# 16_SPI_TYPEC_PWR.net
KiCad netlist of a schematic drawn in Altium Designer
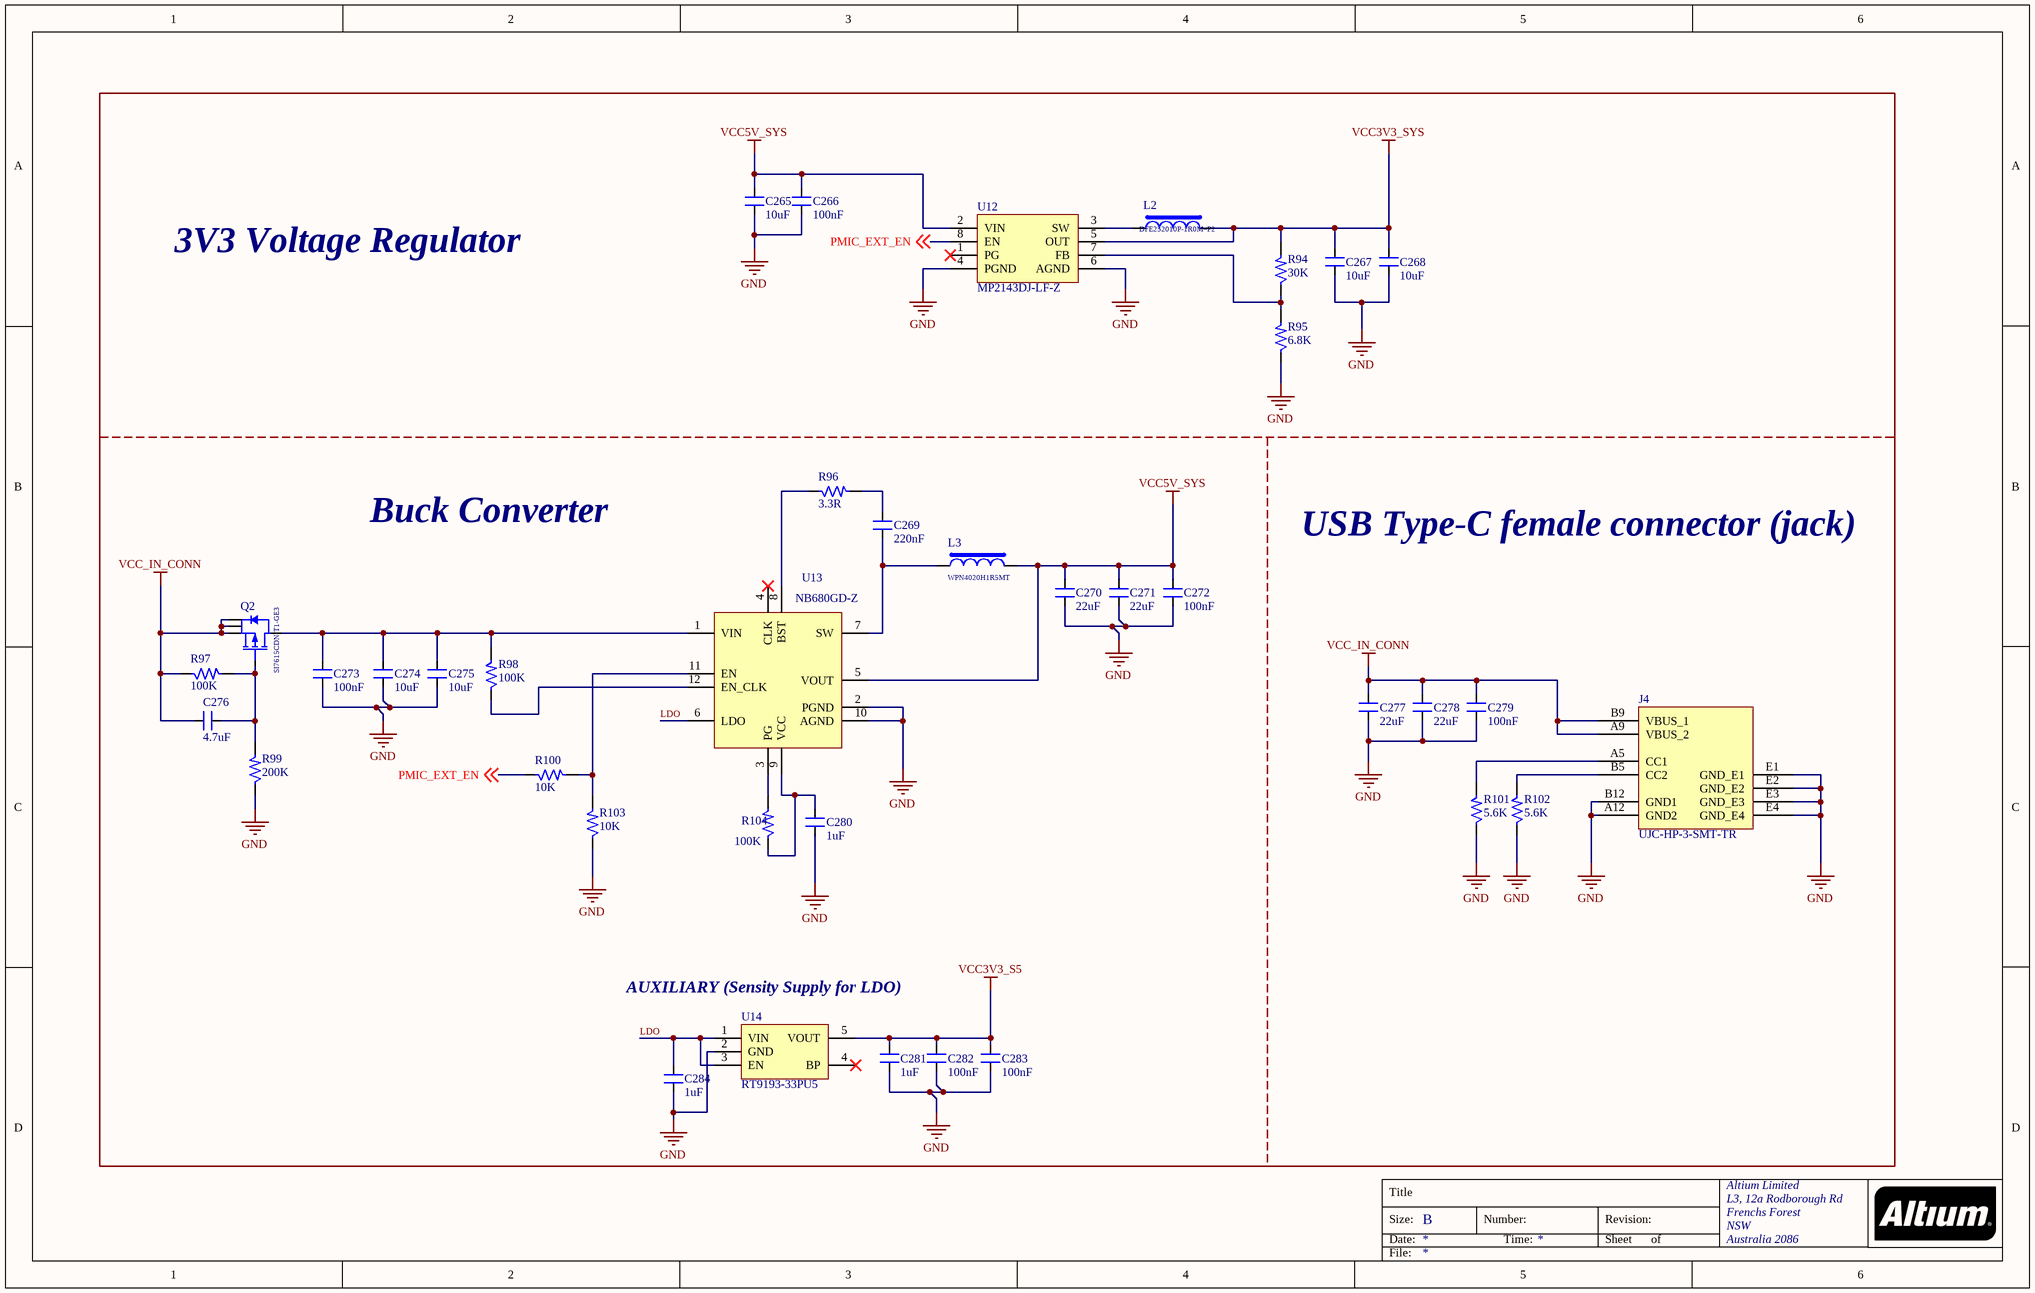
[diagram p0: [16] SPI_TYPEC_PWR.SchDoc]

(export (version "E")
  (design (tool "Eeschema 10.0.6"))
  (components
    (comp (ref "C265")
      (value "10uF")
      (footprint "CAP_0402")
      (description "10µF ±20% 10V Ceramic Capacitor X5R 0402 (1005 Metric)")
      (fields
        (field (name "MANUFACTURER PART NUMBER") "CL05A106MP5NUNC")
        (field (name "MANUFACTURER") "Samsung Electro-Mechanics")
      )
      (libsource (lib "EsteemPCB_SOM_Course_intlib") (part "CAP_10uF-10V-20%-0402"))
    )
    (comp (ref "C266")
      (value "100nF")
      (footprint "CAP_0402")
      (description "0.1µF ±10% 10V Ceramic Capacitor X7R 0402 (1005 Metric)")
      (fields
        (field (name "MANUFACTURER") "Yageo")
        (field (name "MANUFACTURER PART NUMBER") "CC0402KRX7R6BB104")
      )
      (libsource (lib "EsteemPCB_SOM_Course_intlib") (part "CAP_100nF-10V-10%-0402"))
    )
    (comp (ref "C267")
      (value "10uF")
      (footprint "CAP_0402")
      (description "10µF ±20% 10V Ceramic Capacitor X5R 0402 (1005 Metric)")
      (fields
        (field (name "MANUFACTURER PART NUMBER") "CL05A106MP5NUNC")
        (field (name "MANUFACTURER") "Samsung Electro-Mechanics")
      )
      (libsource (lib "EsteemPCB_SOM_Course_intlib") (part "CAP_10uF-10V-20%-0402"))
    )
    (comp (ref "C268")
      (value "10uF")
      (footprint "CAP_0402")
      (description "10µF ±20% 10V Ceramic Capacitor X5R 0402 (1005 Metric)")
      (fields
        (field (name "MANUFACTURER PART NUMBER") "CL05A106MP5NUNC")
        (field (name "MANUFACTURER") "Samsung Electro-Mechanics")
      )
      (libsource (lib "EsteemPCB_SOM_Course_intlib") (part "CAP_10uF-10V-20%-0402"))
    )
    (comp (ref "C269")
      (value "220nF")
      (footprint "CAP_0402")
      (description "0.22µF ±10% 10V Ceramic Capacitor X7R 0402 (1005 Metric)")
      (fields
        (field (name "MANUFACTURER") "Samsung Electro-Mechanics")
        (field (name "MANUFACTURER PART NUMBER") "CL05B224KP5NNNC")
      )
      (libsource (lib "EsteemPCB_SOM_Course_intlib") (part "CAP_220nF-10V-10%-0402"))
    )
    (comp (ref "C270")
      (value "22uF")
      (footprint "CAP_0402")
      (description "22µF ±20% 6.3V Ceramic Capacitor X5R 0402 (1005 Metric)")
      (fields
        (field (name "MANUFACTURER") "Murata Electronics")
        (field (name "MANUFACTURER PART NUMBER") "CL05A226MQ5N6J8")
      )
      (libsource (lib "EsteemPCB_SOM_Course_intlib") (part "CAP_22uF-6.3V-20%-0402"))
    )
    (comp (ref "C271")
      (value "22uF")
      (footprint "CAP_0402")
      (description "22µF ±20% 6.3V Ceramic Capacitor X5R 0402 (1005 Metric)")
      (fields
        (field (name "MANUFACTURER") "Murata Electronics")
        (field (name "MANUFACTURER PART NUMBER") "CL05A226MQ5N6J8")
      )
      (libsource (lib "EsteemPCB_SOM_Course_intlib") (part "CAP_22uF-6.3V-20%-0402"))
    )
    (comp (ref "C272")
      (value "100nF")
      (footprint "CAP_0402")
      (description "0.1µF ±10% 25V Ceramic Capacitor X7R 0402 (1005 Metric)")
      (fields
        (field (name "MANUFACTURER") "Walsin Technology Corporation")
        (field (name "MANUFACTURER PART NUMBER") "0402B104K250CT")
      )
      (libsource (lib "EsteemPCB_SOM_Course_intlib") (part "CAP_100nF-25V-10%-0402"))
    )
    (comp (ref "C273")
      (value "100nF")
      (footprint "CAP_0402")
      (description "0.1µF ±10% 25V Ceramic Capacitor X7R 0402 (1005 Metric)")
      (fields
        (field (name "MANUFACTURER") "Walsin Technology Corporation")
        (field (name "MANUFACTURER PART NUMBER") "0402B104K250CT")
      )
      (libsource (lib "EsteemPCB_SOM_Course_intlib") (part "CAP_100nF-25V-10%-0402"))
    )
    (comp (ref "C274")
      (value "10uF")
      (footprint "CAP_0402")
      (description "10µF ±20% 10V Ceramic Capacitor X5R 0402 (1005 Metric)")
      (fields
        (field (name "MANUFACTURER PART NUMBER") "CL05A106MP5NUNC")
        (field (name "MANUFACTURER") "Samsung Electro-Mechanics")
      )
      (libsource (lib "EsteemPCB_SOM_Course_intlib") (part "CAP_10uF-10V-20%-0402"))
    )
    (comp (ref "C275")
      (value "10uF")
      (footprint "CAP_0402")
      (description "10µF ±20% 10V Ceramic Capacitor X5R 0402 (1005 Metric)")
      (fields
        (field (name "MANUFACTURER PART NUMBER") "CL05A106MP5NUNC")
        (field (name "MANUFACTURER") "Samsung Electro-Mechanics")
      )
      (libsource (lib "EsteemPCB_SOM_Course_intlib") (part "CAP_10uF-10V-20%-0402"))
    )
    (comp (ref "C276")
      (value "4.7uF")
      (footprint "CAP_0402")
      (description "4.7µF ±10% 10V Ceramic Capacitor X5R 0402 (1005 Metric)")
      (fields
        (field (name "MANUFACTURER") "Samsung Electro-Mechanics")
        (field (name "MANUFACTURER PART NUMBER") "CL05A475KP5NRNC")
      )
      (libsource (lib "EsteemPCB_SOM_Course_intlib") (part "CAP_4.7uF-10V-10%-0402"))
    )
    (comp (ref "C277")
      (value "22uF")
      (footprint "CAP_0402")
      (description "22µF ±20% 6.3V Ceramic Capacitor X5R 0402 (1005 Metric)")
      (fields
        (field (name "MANUFACTURER") "Murata Electronics")
        (field (name "MANUFACTURER PART NUMBER") "CL05A226MQ5N6J8")
      )
      (libsource (lib "EsteemPCB_SOM_Course_intlib") (part "CAP_22uF-6.3V-20%-0402"))
    )
    (comp (ref "C278")
      (value "22uF")
      (footprint "CAP_0402")
      (description "22µF ±20% 6.3V Ceramic Capacitor X5R 0402 (1005 Metric)")
      (fields
        (field (name "MANUFACTURER") "Murata Electronics")
        (field (name "MANUFACTURER PART NUMBER") "CL05A226MQ5N6J8")
      )
      (libsource (lib "EsteemPCB_SOM_Course_intlib") (part "CAP_22uF-6.3V-20%-0402"))
    )
    (comp (ref "C279")
      (value "100nF")
      (footprint "CAP_0201")
      (description "0.1µF ±10% 25V Ceramic Capacitor X5R 0201 (0603 Metric)")
      (fields
        (field (name "MANUFACTURER") "TDK Corporation")
        (field (name "MANUFACTURER PART NUMBER") "C0603X5R1E104K030BB")
      )
      (libsource (lib "EsteemPCB_SOM_Course_intlib") (part "CAP_100nF-25V-10%-0201"))
    )
    (comp (ref "C280")
      (value "1uF")
      (footprint "CAP_0402")
      (description "1µF ±10% 16V Ceramic Capacitor X5R 0402 (1005 Metric)")
      (fields
        (field (name "MANUFACTURER") "Knowles Novacap")
        (field (name "MANUFACTURER PART NUMBER") "0402BW105K160YT")
      )
      (libsource (lib "EsteemPCB_SOM_Course_intlib") (part "CAP_1uF-16V-10%-0402"))
    )
    (comp (ref "C281")
      (value "1uF")
      (footprint "CAP_0402")
      (description "1µF ±10% 10V Ceramic Capacitor X6S 0402 (1005 Metric)")
      (fields
        (field (name "MANUFACTURER") "Murata Electronics")
        (field (name "MANUFACTURER PART NUMBER") "GRT155C81A105KE01D")
      )
      (libsource (lib "EsteemPCB_SOM_Course_intlib") (part "CAP_1uF-10V-10%-0402"))
    )
    (comp (ref "C282")
      (value "100nF")
      (footprint "CAP_0402")
      (description "0.1µF ±10% 25V Ceramic Capacitor X7R 0402 (1005 Metric)")
      (fields
        (field (name "MANUFACTURER") "Walsin Technology Corporation")
        (field (name "MANUFACTURER PART NUMBER") "0402B104K250CT")
      )
      (libsource (lib "EsteemPCB_SOM_Course_intlib") (part "CAP_100nF-25V-10%-0402"))
    )
    (comp (ref "C283")
      (value "100nF")
      (footprint "CAP_0402")
      (description "0.1µF ±10% 25V Ceramic Capacitor X7R 0402 (1005 Metric)")
      (fields
        (field (name "MANUFACTURER") "Walsin Technology Corporation")
        (field (name "MANUFACTURER PART NUMBER") "0402B104K250CT")
      )
      (libsource (lib "EsteemPCB_SOM_Course_intlib") (part "CAP_100nF-25V-10%-0402"))
    )
    (comp (ref "C284")
      (value "1uF")
      (footprint "CAP_0402")
      (description "1µF ±10% 10V Ceramic Capacitor X6S 0402 (1005 Metric)")
      (fields
        (field (name "MANUFACTURER") "Murata Electronics")
        (field (name "MANUFACTURER PART NUMBER") "GRT155C81A105KE01D")
      )
      (libsource (lib "EsteemPCB_SOM_Course_intlib") (part "CAP_1uF-10V-10%-0402"))
    )
    (comp (ref "J4")
      (value "UJC-HP-3-SMT-TR")
      (footprint "CON6_48.4_UJC-HP-3-SMT-TR")
      (fields (field (name "MANUFACTURER") "CUI Devices"))
      (libsource (lib "EsteemPCB_SOM_Course_intlib") (part "CON-TYPEC_6X1-100-RA-TH"))
    )
    (comp (ref "L2")
      (value "DFE252010P-1R0M=P2")
      (footprint "IND_1008")
      (description "1µH Shielded Wirewound Inductor 3.8A 54mOhm Max 1008 (2520 Metric)")
      (fields (field (name "MANUFACTURER") "Murata Electronics"))
      (libsource (lib "EsteemPCB_SOM_Course_intlib") (part "IND_1uH-3.8A-20%-1008"))
    )
    (comp (ref "L3")
      (value "WPN4020H1R5MT")
      (footprint "IND_1616")
      (fields (field (name "MANUFACTURER") "Sunlord"))
      (libsource (lib "EsteemPCB_SOM_Course_intlib") (part "IND_1.5uH-6A-20%-SMD"))
    )
    (comp (ref "Q2")
      (value "SI7615CDN-T1-GE3")
      (footprint "PowerPAK_1212-8_SMD")
      (description "P-Channel 20V 35A (Tc) 33W (Tc) Surface Mount PowerPAK® 1212-8")
      (fields (field (name "MANUFACTURER") "Vishay Siliconix"))
      (libsource (lib "EsteemPCB_SOM_Course_intlib") (part "MOSFET-P_20V-35A-1212-8"))
    )
    (comp (ref "R94")
      (value "30K")
      (footprint "RES_0402")
      (fields
        (field (name "MANUFACTURER") "KOA Speer Electronics, Inc.")
        (field (name "MANUFACTURER PART NUMBER") "RK73H1ETTP3002F")
      )
      (libsource (lib "EsteemPCB_SOM_Course_intlib") (part "RES_30K-0.1W-1%-0402"))
    )
    (comp (ref "R95")
      (value "6.8K")
      (footprint "RES_0402")
      (description "6.8 kOhms ±1% 0.1W, 1/10W Chip Resistor 0402 (1005 Metric) Anti-Sulfur Thin Film")
      (fields
        (field (name "MANUFACTURER") "Vishay Beyschlag/Draloric/BC Components")
        (field (name "MANUFACTURER PART NUMBER") "MCS04020C6801FE000")
      )
      (libsource (lib "EsteemPCB_SOM_Course_intlib") (part "RES_6.8K-0.1W-1%-0402"))
    )
    (comp (ref "R96")
      (value "3.3R")
      (footprint "RES_0402")
      (fields
        (field (name "MANUFACTURER") "Panasonic Electronic Components")
        (field (name "MANUFACTURER PART NUMBER") "ERJ-U02F3R30X")
      )
      (libsource (lib "EsteemPCB_SOM_Course_intlib") (part "RES_3.3R-0.1W-1%-0402"))
    )
    (comp (ref "R97")
      (value "100K")
      (footprint "RES_0402")
      (description "100 kOhms ±1% 0.1W, 1/10W Chip Resistor 0402 (1005 Metric) Anti-Sulfur Thin Film")
      (fields
        (field (name "MANUFACTURER") "Vishay Beyschlag/Draloric/BC Components")
        (field (name "MANUFACTURER PART NUMBER") "MCS04020C1003FE000")
      )
      (libsource (lib "EsteemPCB_SOM_Course_intlib") (part "RES_100K-0.1W-1%-0402"))
    )
    (comp (ref "R98")
      (value "100K")
      (footprint "RES_0402")
      (description "100 kOhms ±1% 0.1W, 1/10W Chip Resistor 0402 (1005 Metric) Anti-Sulfur Thin Film")
      (fields
        (field (name "MANUFACTURER") "Vishay Beyschlag/Draloric/BC Components")
        (field (name "MANUFACTURER PART NUMBER") "MCS04020C1003FE000")
      )
      (libsource (lib "EsteemPCB_SOM_Course_intlib") (part "RES_100K-0.1W-1%-0402"))
    )
    (comp (ref "R99")
      (value "200K")
      (footprint "RES_0402")
      (description "200 kOhms ±1% 0.1W, 1/10W Chip Resistor 0402 (1005 Metric) Automotive AEC-Q200 Thick Film")
      (fields
        (field (name "MANUFACTURER") "Panasonic Electronic Components")
        (field (name "MANUFACTURER PART NUMBER") "ERJ-2RKF2003X")
      )
      (libsource (lib "EsteemPCB_SOM_Course_intlib") (part "RES_200K-0.1W-1%-0402"))
    )
    (comp (ref "R100")
      (value "10K")
      (footprint "RES_0402")
      (description "10 kOhms ±1% 0.1W, 1/10W Chip Resistor 0402 (1005 Metric) Anti-Sulfur Thin Film")
      (fields
        (field (name "MANUFACTURER") "Vishay Beyschlag/Draloric/BC Components")
        (field (name "MANUFACTURER PART NUMBER") "MCS04020C1002FE000")
      )
      (libsource (lib "EsteemPCB_SOM_Course_intlib") (part "RES_10K-0.1W-1%-0402"))
    )
    (comp (ref "R101")
      (value "5.6K")
      (footprint "RES_0201")
      (description "5.6 kOhms ±1% 0.05W, 1/20W Chip Resistor 0201 (0603 Metric) Automotive AEC-Q200 Thick Film")
      (fields
        (field (name "MANUFACTURER") "Panasonic Electronic Components")
        (field (name "MANUFACTURER PART NUMBER") "ERJ-1GNF5601C")
      )
      (libsource (lib "EsteemPCB_SOM_Course_intlib") (part "RES_5.6K-0.05W-1%-0201"))
    )
    (comp (ref "R102")
      (value "5.6K")
      (footprint "RES_0201")
      (description "5.6 kOhms ±1% 0.05W, 1/20W Chip Resistor 0201 (0603 Metric) Automotive AEC-Q200 Thick Film")
      (fields
        (field (name "MANUFACTURER") "Panasonic Electronic Components")
        (field (name "MANUFACTURER PART NUMBER") "ERJ-1GNF5601C")
      )
      (libsource (lib "EsteemPCB_SOM_Course_intlib") (part "RES_5.6K-0.05W-1%-0201"))
    )
    (comp (ref "R103")
      (value "10K")
      (footprint "RES_0402")
      (description "10 kOhms ±1% 0.1W, 1/10W Chip Resistor 0402 (1005 Metric) Anti-Sulfur Thin Film")
      (fields
        (field (name "MANUFACTURER") "Vishay Beyschlag/Draloric/BC Components")
        (field (name "MANUFACTURER PART NUMBER") "MCS04020C1002FE000")
      )
      (libsource (lib "EsteemPCB_SOM_Course_intlib") (part "RES_10K-0.1W-1%-0402"))
    )
    (comp (ref "R104")
      (value "100K")
      (footprint "RES_0402")
      (description "100 kOhms ±1% 0.1W, 1/10W Chip Resistor 0402 (1005 Metric) Anti-Sulfur Thin Film")
      (fields
        (field (name "MANUFACTURER") "Vishay Beyschlag/Draloric/BC Components")
        (field (name "MANUFACTURER PART NUMBER") "MCS04020C1003FE000")
      )
      (libsource (lib "EsteemPCB_SOM_Course_intlib") (part "RES_100K-0.1W-1%-0402"))
    )
    (comp (ref "U12")
      (value "MP2143DJ-LF-Z")
      (footprint "SOT23-8")
      (description "Switching Voltage Regulators 3A, 5.5V, 1.2MHz Sync Stp-Dwn Swtchr")
      (fields (field (name "MANUFACTURER") "Monolithic Power Systems (MPS)"))
      (libsource (lib "EsteemPCB_SOM_Course_intlib") (part "REG_0.6~5V-5.5V-3A-TSOT-23-8"))
    )
    (comp (ref "U13")
      (value "NB680GD-Z")
      (footprint "QFN-12_19_118X118_SMD")
      (description "Switching Voltage Regulators 26V Fixed 3.3 V-8A Sync Buck Converter")
      (fields (field (name "MANUFACTURER") "Monolithic Power Systems (MPS)"))
      (libsource (lib "EsteemPCB_SOM_Course_intlib") (part "REG_3.3V-26V-8A-QFN-12"))
    )
    (comp (ref "U14")
      (value "RT9193-33PU5")
      (footprint "SC70-5")
      (description "SC-70-5 Dropout Regulators(LDO) RoHS")
      (fields (field (name "MANUFACTURER") "Richtek Tech"))
      (libsource (lib "EsteemPCB_SOM_Course_intlib") (part "REG_3.3V-5.5V-300mA-SC-70-5"))
    )
  )
  (nets
    (net (code "1") (name "/LDO") (class "Default")
      (node (ref "C284") (pin "2") (pinfunction "2_2") (pintype "passive"))
      (node (ref "U13") (pin "6") (pinfunction "LDO_6") (pintype "passive"))
      (node (ref "U14") (pin "1") (pinfunction "VIN_1") (pintype "passive"))
      (node (ref "U14") (pin "3") (pinfunction "EN_3") (pintype "passive"))
    )
    (net (code "2") (name "GND") (class "Default")
      (node (ref "C265") (pin "1") (pinfunction "1_1") (pintype "passive"))
      (node (ref "C266") (pin "1") (pinfunction "1_1") (pintype "passive"))
      (node (ref "C267") (pin "1") (pinfunction "1_1") (pintype "passive"))
      (node (ref "C268") (pin "1") (pinfunction "1_1") (pintype "passive"))
      (node (ref "C270") (pin "1") (pinfunction "1_1") (pintype "passive"))
      (node (ref "C271") (pin "1") (pinfunction "1_1") (pintype "passive"))
      (node (ref "C272") (pin "1") (pinfunction "1_1") (pintype "passive"))
      (node (ref "C273") (pin "1") (pinfunction "1_1") (pintype "passive"))
      (node (ref "C274") (pin "1") (pinfunction "1_1") (pintype "passive"))
      (node (ref "C275") (pin "1") (pinfunction "1_1") (pintype "passive"))
      (node (ref "C277") (pin "1") (pinfunction "1_1") (pintype "passive"))
      (node (ref "C278") (pin "1") (pinfunction "1_1") (pintype "passive"))
      (node (ref "C279") (pin "1") (pinfunction "1_1") (pintype "passive"))
      (node (ref "C280") (pin "1") (pinfunction "1_1") (pintype "passive"))
      (node (ref "C281") (pin "1") (pinfunction "1_1") (pintype "passive"))
      (node (ref "C282") (pin "1") (pinfunction "1_1") (pintype "passive"))
      (node (ref "C283") (pin "1") (pinfunction "1_1") (pintype "passive"))
      (node (ref "C284") (pin "1") (pinfunction "1_1") (pintype "passive"))
      (node (ref "J4") (pin "A12") (pinfunction "GND2_A12") (pintype "passive"))
      (node (ref "J4") (pin "B12") (pinfunction "GND1_B12") (pintype "passive"))
      (node (ref "J4") (pin "E1") (pinfunction "GND_E1_E1") (pintype "passive"))
      (node (ref "J4") (pin "E2") (pinfunction "GND_E2_E2") (pintype "passive"))
      (node (ref "J4") (pin "E3") (pinfunction "GND_E3_E3") (pintype "passive"))
      (node (ref "J4") (pin "E4") (pinfunction "GND_E4_E4") (pintype "passive"))
      (node (ref "R101") (pin "1") (pinfunction "1_1") (pintype "passive"))
      (node (ref "R102") (pin "1") (pinfunction "1_1") (pintype "passive"))
      (node (ref "R103") (pin "1") (pinfunction "1_1") (pintype "passive"))
      (node (ref "R95") (pin "1") (pinfunction "1_1") (pintype "passive"))
      (node (ref "R99") (pin "1") (pinfunction "1_1") (pintype "passive"))
      (node (ref "U12") (pin "4") (pinfunction "PGND_4") (pintype "passive"))
      (node (ref "U12") (pin "6") (pinfunction "AGND_6") (pintype "passive"))
      (node (ref "U13") (pin "10") (pinfunction "AGND_10") (pintype "passive"))
      (node (ref "U13") (pin "2") (pinfunction "PGND_2") (pintype "passive"))
      (node (ref "U14") (pin "2") (pinfunction "GND_2") (pintype "passive"))
    )
    (net (code "3") (name "Net-(C269-Pad2)") (class "Default")
      (node (ref "C269") (pin "2") (pinfunction "2_2") (pintype "passive"))
      (node (ref "R96") (pin "2") (pinfunction "2_2") (pintype "passive"))
    )
    (net (code "4") (name "Net-(J4-CC1)") (class "Default")
      (node (ref "J4") (pin "A5") (pinfunction "CC1_A5") (pintype "passive"))
      (node (ref "R101") (pin "2") (pinfunction "2_2") (pintype "passive"))
    )
    (net (code "5") (name "Net-(J4-CC2)") (class "Default")
      (node (ref "J4") (pin "B5") (pinfunction "CC2_B5") (pintype "passive"))
      (node (ref "R102") (pin "2") (pinfunction "2_2") (pintype "passive"))
    )
    (net (code "6") (name "Net-(Q2-D)") (class "Default")
      (node (ref "C273") (pin "2") (pinfunction "2_2") (pintype "passive"))
      (node (ref "C274") (pin "2") (pinfunction "2_2") (pintype "passive"))
      (node (ref "C275") (pin "2") (pinfunction "2_2") (pintype "passive"))
      (node (ref "Q2") (pin "5") (pinfunction "D_5") (pintype "passive"))
      (node (ref "R98") (pin "2") (pinfunction "2_2") (pintype "passive"))
      (node (ref "U13") (pin "1") (pinfunction "VIN_1") (pintype "passive"))
    )
    (net (code "7") (name "Net-(Q2-G)") (class "Default")
      (node (ref "C276") (pin "2") (pinfunction "2_2") (pintype "passive"))
      (node (ref "Q2") (pin "4") (pinfunction "G_4") (pintype "passive"))
      (node (ref "R97") (pin "2") (pinfunction "2_2") (pintype "passive"))
      (node (ref "R99") (pin "2") (pinfunction "2_2") (pintype "passive"))
    )
    (net (code "8") (name "Net-(U12-FB)") (class "Default")
      (node (ref "R94") (pin "1") (pinfunction "1_1") (pintype "passive"))
      (node (ref "R95") (pin "2") (pinfunction "2_2") (pintype "passive"))
      (node (ref "U12") (pin "7") (pinfunction "FB_7") (pintype "passive"))
    )
    (net (code "9") (name "Net-(U12-SW)") (class "Default")
      (node (ref "L2") (pin "1") (pinfunction "1_1") (pintype "passive"))
      (node (ref "U12") (pin "3") (pinfunction "SW_3") (pintype "passive"))
    )
    (net (code "10") (name "Net-(U13-BST)") (class "Default")
      (node (ref "R96") (pin "1") (pinfunction "1_1") (pintype "passive"))
      (node (ref "U13") (pin "8") (pinfunction "BST_8") (pintype "passive"))
    )
    (net (code "11") (name "Net-(U13-EN)") (class "Default")
      (node (ref "R100") (pin "2") (pinfunction "2_2") (pintype "passive"))
      (node (ref "R103") (pin "2") (pinfunction "2_2") (pintype "passive"))
      (node (ref "U13") (pin "11") (pinfunction "EN_11") (pintype "passive"))
    )
    (net (code "12") (name "Net-(U13-EN_CLK)") (class "Default")
      (node (ref "R98") (pin "1") (pinfunction "1_1") (pintype "passive"))
      (node (ref "U13") (pin "12") (pinfunction "EN_CLK_12") (pintype "passive"))
    )
    (net (code "13") (name "Net-(U13-PG)") (class "Default")
      (node (ref "R104") (pin "2") (pinfunction "2_2") (pintype "passive"))
      (node (ref "U13") (pin "3") (pinfunction "PG_3") (pintype "passive"))
    )
    (net (code "14") (name "Net-(U13-SW)") (class "Default")
      (node (ref "C269") (pin "1") (pinfunction "1_1") (pintype "passive"))
      (node (ref "L3") (pin "1") (pinfunction "1_1") (pintype "passive"))
      (node (ref "U13") (pin "7") (pinfunction "SW_7") (pintype "passive"))
    )
    (net (code "15") (name "Net-(U13-VCC)") (class "Default")
      (node (ref "C280") (pin "2") (pinfunction "2_2") (pintype "passive"))
      (node (ref "R104") (pin "1") (pinfunction "1_1") (pintype "passive"))
      (node (ref "U13") (pin "9") (pinfunction "VCC_9") (pintype "passive"))
    )
    (net (code "16") (name "PMIC_EXT_EN") (class "Default")
      (node (ref "R100") (pin "1") (pinfunction "1_1") (pintype "passive"))
      (node (ref "U12") (pin "8") (pinfunction "EN_8") (pintype "passive"))
    )
    (net (code "17") (name "VCC3V3_S5") (class "Default")
      (node (ref "C281") (pin "2") (pinfunction "2_2") (pintype "passive"))
      (node (ref "C282") (pin "2") (pinfunction "2_2") (pintype "passive"))
      (node (ref "C283") (pin "2") (pinfunction "2_2") (pintype "passive"))
      (node (ref "U14") (pin "5") (pinfunction "VOUT_5") (pintype "passive"))
    )
    (net (code "18") (name "VCC3V3_SYS") (class "Default")
      (node (ref "C267") (pin "2") (pinfunction "2_2") (pintype "passive"))
      (node (ref "C268") (pin "2") (pinfunction "2_2") (pintype "passive"))
      (node (ref "L2") (pin "2") (pinfunction "2_2") (pintype "passive"))
      (node (ref "R94") (pin "2") (pinfunction "2_2") (pintype "passive"))
      (node (ref "U12") (pin "5") (pinfunction "OUT_5") (pintype "passive"))
    )
    (net (code "19") (name "VCC5V_SYS") (class "Default")
      (node (ref "C265") (pin "2") (pinfunction "2_2") (pintype "passive"))
      (node (ref "C266") (pin "2") (pinfunction "2_2") (pintype "passive"))
      (node (ref "C270") (pin "2") (pinfunction "2_2") (pintype "passive"))
      (node (ref "C271") (pin "2") (pinfunction "2_2") (pintype "passive"))
      (node (ref "C272") (pin "2") (pinfunction "2_2") (pintype "passive"))
      (node (ref "L3") (pin "2") (pinfunction "2_2") (pintype "passive"))
      (node (ref "U12") (pin "2") (pinfunction "VIN_2") (pintype "passive"))
      (node (ref "U13") (pin "5") (pinfunction "VOUT_5") (pintype "passive"))
    )
    (net (code "20") (name "VCC_IN_CONN") (class "Default")
      (node (ref "C276") (pin "1") (pinfunction "1_1") (pintype "passive"))
      (node (ref "C277") (pin "2") (pinfunction "2_2") (pintype "passive"))
      (node (ref "C278") (pin "2") (pinfunction "2_2") (pintype "passive"))
      (node (ref "C279") (pin "2") (pinfunction "2_2") (pintype "passive"))
      (node (ref "J4") (pin "A9") (pinfunction "VBUS_2_A9") (pintype "passive"))
      (node (ref "J4") (pin "B9") (pinfunction "VBUS_1_B9") (pintype "passive"))
      (node (ref "Q2") (pin "1") (pinfunction "S_1") (pintype "passive"))
      (node (ref "Q2") (pin "2") (pinfunction "S_2") (pintype "passive"))
      (node (ref "Q2") (pin "3") (pinfunction "S_3") (pintype "passive"))
      (node (ref "R97") (pin "1") (pinfunction "1_1") (pintype "passive"))
    )
    (net (code "21") (name "unconnected-(U12-PG-Pad1)") (class "Default")
      (node (ref "U12") (pin "1") (pinfunction "PG_1") (pintype "passive+no_connect"))
    )
    (net (code "22") (name "unconnected-(U13-CLK-Pad4)") (class "Default")
      (node (ref "U13") (pin "4") (pinfunction "CLK_4") (pintype "passive+no_connect"))
    )
    (net (code "23") (name "unconnected-(U14-BP-Pad4)") (class "Default")
      (node (ref "U14") (pin "4") (pinfunction "BP_4") (pintype "passive+no_connect"))
    )
  )
)
